# charge_controller.net
KiCad netlist of a schematic drawn in Altium Designer
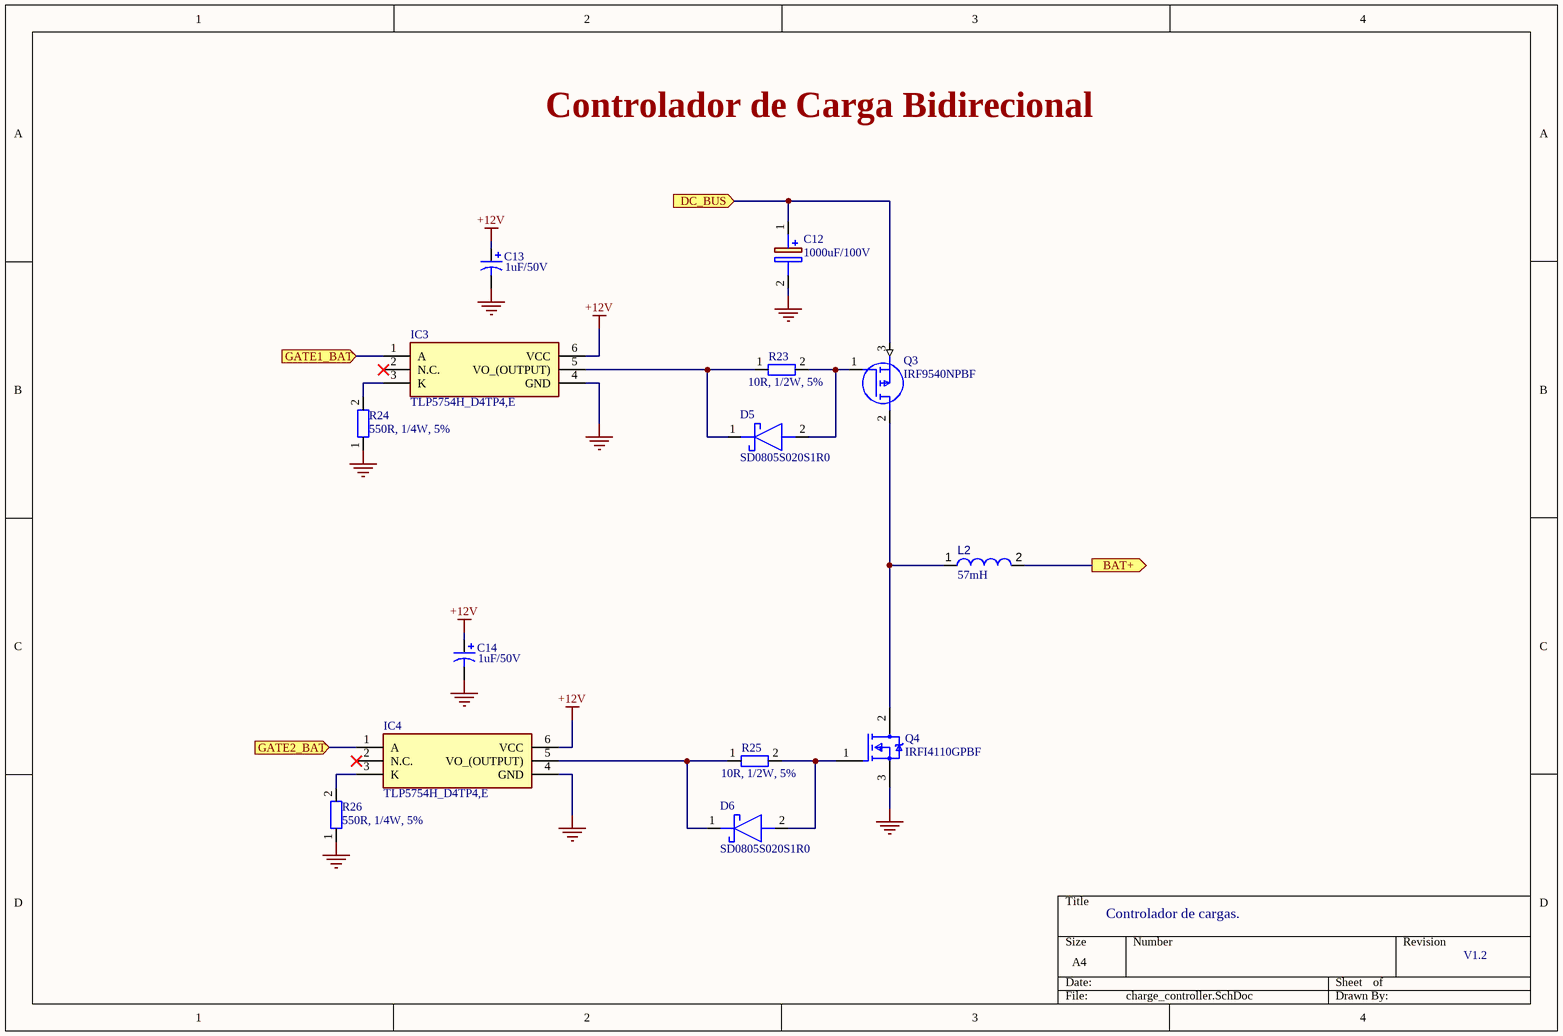
[diagram p0: charge_controller.SchDoc]

(export (version "E")
  (design (tool "Eeschema 10.0.6"))
  (components
    (comp (ref "C12")
      (value "1000uF/100V")
      (footprint "PcbLib1:CAPPRD750W85D1800H3750")
      (description "Aluminum Electrolytic Capacitors - Leaded 1000uF 100V")
      (fields
        (field (name "MANUFACTURER_PART_NUMBER") "ECA-2AHG102")
        (field (name "MOUSER PART NUMBER") "667-ECA-2AHG102")
      )
      (libsource (lib "*") (part "ECA-2AHG102"))
    )
    (comp (ref "C13")
      (value "1uF/50V")
      (footprint "C1206")
      (fields
        (field (name "MANUFACTURER") "KEMET")
        (field (name "MANUFACTURER PART NUMBER") "T491A105K050AT")
        (field (name "TOLERANCE") "10%")
        (field (name "PUBLISHER") "Altium Limited")
      )
      (libsource (lib "Miscellaneous Devices") (part "Cap Pol1"))
    )
    (comp (ref "C14")
      (value "1uF/50V")
      (footprint "C1206")
      (fields
        (field (name "MANUFACTURER") "KEMET")
        (field (name "MANUFACTURER PART NUMBER") "T491A105K050AT")
        (field (name "TOLERANCE") "10%")
        (field (name "PUBLISHER") "Altium Limited")
      )
      (libsource (lib "Miscellaneous Devices") (part "Cap Pol1"))
    )
    (comp (ref "D5")
      (value "SD0805S020S1R0")
      (footprint "PcbLib1:DIOM1613X100N")
      (description "Schottky Diodes & Rectifiers 20volts 1A SIZE 0805")
      (fields
        (field (name "MOUSER PART NUMBER") "581-SD0805S020S1R0")
        (field (name "MANUFACTURER") "Kyocera AVX")
      )
      (libsource (lib "*") (part "SD0805S020S1R0"))
    )
    (comp (ref "D6")
      (value "SD0805S020S1R0")
      (footprint "PcbLib1:DIOM1613X100N")
      (description "Schottky Diodes & Rectifiers 20volts 1A SIZE 0805")
      (fields
        (field (name "MOUSER PART NUMBER") "581-SD0805S020S1R0")
        (field (name "MANUFACTURER") "Kyocera AVX")
      )
      (libsource (lib "*") (part "SD0805S020S1R0"))
    )
    (comp (ref "IC3")
      (value "TLP5754H_D4TP4,E")
      (footprint "PcbLib1:SOIC127P1105X230-6N")
      (description "Integrated Circuit")
      (fields
        (field (name "MANUFACTURER_PART_NUMBER") "TLP5754H(D4TP4,E")
        (field (name "MOUSER PART NUMBER") "757-TLP5754HD4TP4E")
      )
      (libsource (lib "*") (part "TLP5754H_D4TP4,E"))
    )
    (comp (ref "IC4")
      (value "TLP5754H_D4TP4,E")
      (footprint "PcbLib1:SOIC127P1105X230-6N")
      (description "Integrated Circuit")
      (fields
        (field (name "MANUFACTURER_PART_NUMBER") "TLP5754H(D4TP4,E")
        (field (name "MOUSER PART NUMBER") "757-TLP5754HD4TP4E")
      )
      (libsource (lib "*") (part "TLP5754H_D4TP4,E"))
    )
    (comp (ref "L2")
      (value "57mH")
      (footprint "INDR62-500-1100X850X1100")
      (description "Radial Inductor, 100 uH, +/- 10%, 0.91 A, -55 to 105 degC, 2-Pin THD, RoHS, Bulk")
      (fields (field (name "TOLERANCE") "10%") (field (name "MANUFACTURER") "Bourns"))
      (libsource (lib "PI2") (part "IND-2"))
    )
    (comp (ref "Q3")
      (value "IRF9540NPBF")
      (footprint "PcbLib1:TO254P469X1042X1967-3P")
      (description "Mosfet, Power; P-ch; Vdss -100V; Rds(on) 0.117 Ohm; Id -23A; TO-220AB; Pd 140W; Vgs +/-2")
      (fields
        (field (name "MOUSER PART NUMBER") "942-IRF9540NPBF")
        (field (name "MANUFACTURER") "International Rectifier")
      )
      (libsource (lib "*") (part "IRF9540NPBF"))
    )
    (comp (ref "Q4")
      (value "IRFI4110GPBF")
      (footprint "FP-PG-TO220-3-MFG")
      (description "MOSFET N-CH 100V 72A TO220AB")
      (fields (field (name "MANUFACTURER") "Infineon"))
      (libsource (lib "Altium Content Vault") (part "8b62d417cbef8344eebe0bde0c45977"))
    )
    (comp (ref "R23")
      (value "10R, 1/2W, 5%")
      (footprint "PcbLib1:RES-0805")
      (description "Res Thick Film 2512 10 Ohm 5% 1W 200ppm/C Molded SMD SMD Blister T/R")
      (fields
        (field (name "MANUFACTURER_PART_NUMBER") "RC0805JR-131KL")
        (field (name "MOUSER PART NUMBER") "603-RC0805JR-131KL")
      )
      (libsource (lib "pi2") (part "Res-0805"))
    )
    (comp (ref "R24")
      (value "550R, 1/4W, 5%")
      (footprint "PcbLib1:RES-0805")
      (description "RES SMD 560 MOHM 5% 1/8W 0805")
      (fields
        (field (name "MANUFACTURER_PART_NUMBER") "RC0805JR-131KL")
        (field (name "MOUSER PART NUMBER") "603-RC0805JR-131KL")
      )
      (libsource (lib "") (part "Res-0805_1"))
    )
    (comp (ref "R25")
      (value "10R, 1/2W, 5%")
      (footprint "PcbLib1:RES-0805")
      (description "Res Thick Film 2512 10 Ohm 5% 1W 200ppm/C Molded SMD SMD Blister T/R")
      (fields
        (field (name "MANUFACTURER_PART_NUMBER") "RC0805JR-131KL")
        (field (name "MOUSER PART NUMBER") "603-RC0805JR-131KL")
      )
      (libsource (lib "pi2") (part "Res-0805"))
    )
    (comp (ref "R26")
      (value "550R, 1/4W, 5%")
      (footprint "PcbLib1:RES-0805")
      (description "RES SMD 560 MOHM 5% 1/8W 0805")
      (fields
        (field (name "MANUFACTURER_PART_NUMBER") "RC0805JR-131KL")
        (field (name "MOUSER PART NUMBER") "603-RC0805JR-131KL")
      )
      (libsource (lib "") (part "Res-0805_1"))
    )
  )
  (nets
    (net (code "1") (name "+12V") (class "Default")
      (node (ref "C13") (pin "1") (pinfunction "1_1") (pintype "passive"))
      (node (ref "C14") (pin "1") (pinfunction "1_1") (pintype "passive"))
      (node (ref "IC3") (pin "6") (pinfunction "VCC_6") (pintype "passive"))
      (node (ref "IC4") (pin "6") (pinfunction "VCC_6") (pintype "passive"))
    )
    (net (code "2") (name "/BAT+") (class "Default")
      (node (ref "L2") (pin "2") (pinfunction "2_2") (pintype "passive"))
    )
    (net (code "3") (name "/DC_BUS") (class "Default")
      (node (ref "C12") (pin "1") (pinfunction "+_1") (pintype "passive"))
      (node (ref "Q3") (pin "3") (pinfunction "S_3") (pintype "input"))
    )
    (net (code "4") (name "/GATE1_BAT") (class "Default")
      (node (ref "IC3") (pin "1") (pinfunction "A_1") (pintype "passive"))
    )
    (net (code "5") (name "/GATE2_BAT") (class "Default")
      (node (ref "IC4") (pin "1") (pinfunction "A_1") (pintype "passive"))
    )
    (net (code "6") (name "GND") (class "Default")
      (node (ref "C12") (pin "2") (pinfunction "-_2") (pintype "passive"))
      (node (ref "C13") (pin "2") (pinfunction "2_2") (pintype "passive"))
      (node (ref "C14") (pin "2") (pinfunction "2_2") (pintype "passive"))
      (node (ref "IC3") (pin "4") (pinfunction "GND_4") (pintype "passive"))
      (node (ref "IC4") (pin "4") (pinfunction "GND_4") (pintype "passive"))
      (node (ref "Q4") (pin "3") (pinfunction "SOURCE_3") (pintype "passive"))
      (node (ref "R24") (pin "1") (pinfunction "1_1") (pintype "passive"))
      (node (ref "R26") (pin "1") (pinfunction "1_1") (pintype "passive"))
    )
    (net (code "7") (name "Net-(D5-A)") (class "Default")
      (node (ref "D5") (pin "2") (pinfunction "A_2") (pintype "passive"))
      (node (ref "Q3") (pin "1") (pinfunction "G_1") (pintype "power_in"))
      (node (ref "R23") (pin "2") (pinfunction "2_2") (pintype "passive"))
    )
    (net (code "8") (name "Net-(D5-K)") (class "Default")
      (node (ref "D5") (pin "1") (pinfunction "K_1") (pintype "passive"))
      (node (ref "IC3") (pin "5") (pinfunction "VO_(OUTPUT)_5") (pintype "passive"))
      (node (ref "R23") (pin "1") (pinfunction "1_1") (pintype "passive"))
    )
    (net (code "9") (name "Net-(D6-A)") (class "Default")
      (node (ref "D6") (pin "2") (pinfunction "A_2") (pintype "passive"))
      (node (ref "Q4") (pin "1") (pinfunction "GATE_1") (pintype "passive"))
      (node (ref "R25") (pin "2") (pinfunction "2_2") (pintype "passive"))
    )
    (net (code "10") (name "Net-(D6-K)") (class "Default")
      (node (ref "D6") (pin "1") (pinfunction "K_1") (pintype "passive"))
      (node (ref "IC4") (pin "5") (pinfunction "VO_(OUTPUT)_5") (pintype "passive"))
      (node (ref "R25") (pin "1") (pinfunction "1_1") (pintype "passive"))
    )
    (net (code "11") (name "Net-(IC3-K)") (class "Default")
      (node (ref "IC3") (pin "3") (pinfunction "K_3") (pintype "passive"))
      (node (ref "R24") (pin "2") (pinfunction "2_2") (pintype "passive"))
    )
    (net (code "12") (name "Net-(IC4-K)") (class "Default")
      (node (ref "IC4") (pin "3") (pinfunction "K_3") (pintype "passive"))
      (node (ref "R26") (pin "2") (pinfunction "2_2") (pintype "passive"))
    )
    (net (code "13") (name "Net-(Q3-D)") (class "Default")
      (node (ref "L2") (pin "1") (pinfunction "1_1") (pintype "passive"))
      (node (ref "Q3") (pin "2") (pinfunction "D_2") (pintype "power_in"))
      (node (ref "Q4") (pin "2") (pinfunction "DRAIN_2") (pintype "passive"))
    )
    (net (code "14") (name "unconnected-(IC3-N.C.-Pad2)") (class "Default")
      (node (ref "IC3") (pin "2") (pinfunction "N.C._2") (pintype "passive+no_connect"))
    )
    (net (code "15") (name "unconnected-(IC4-N.C.-Pad2)") (class "Default")
      (node (ref "IC4") (pin "2") (pinfunction "N.C._2") (pintype "passive+no_connect"))
    )
  )
)
